# SCH_New-Project_2024-08-15.net
KiCad netlist of a schematic drawn in EasyEDA
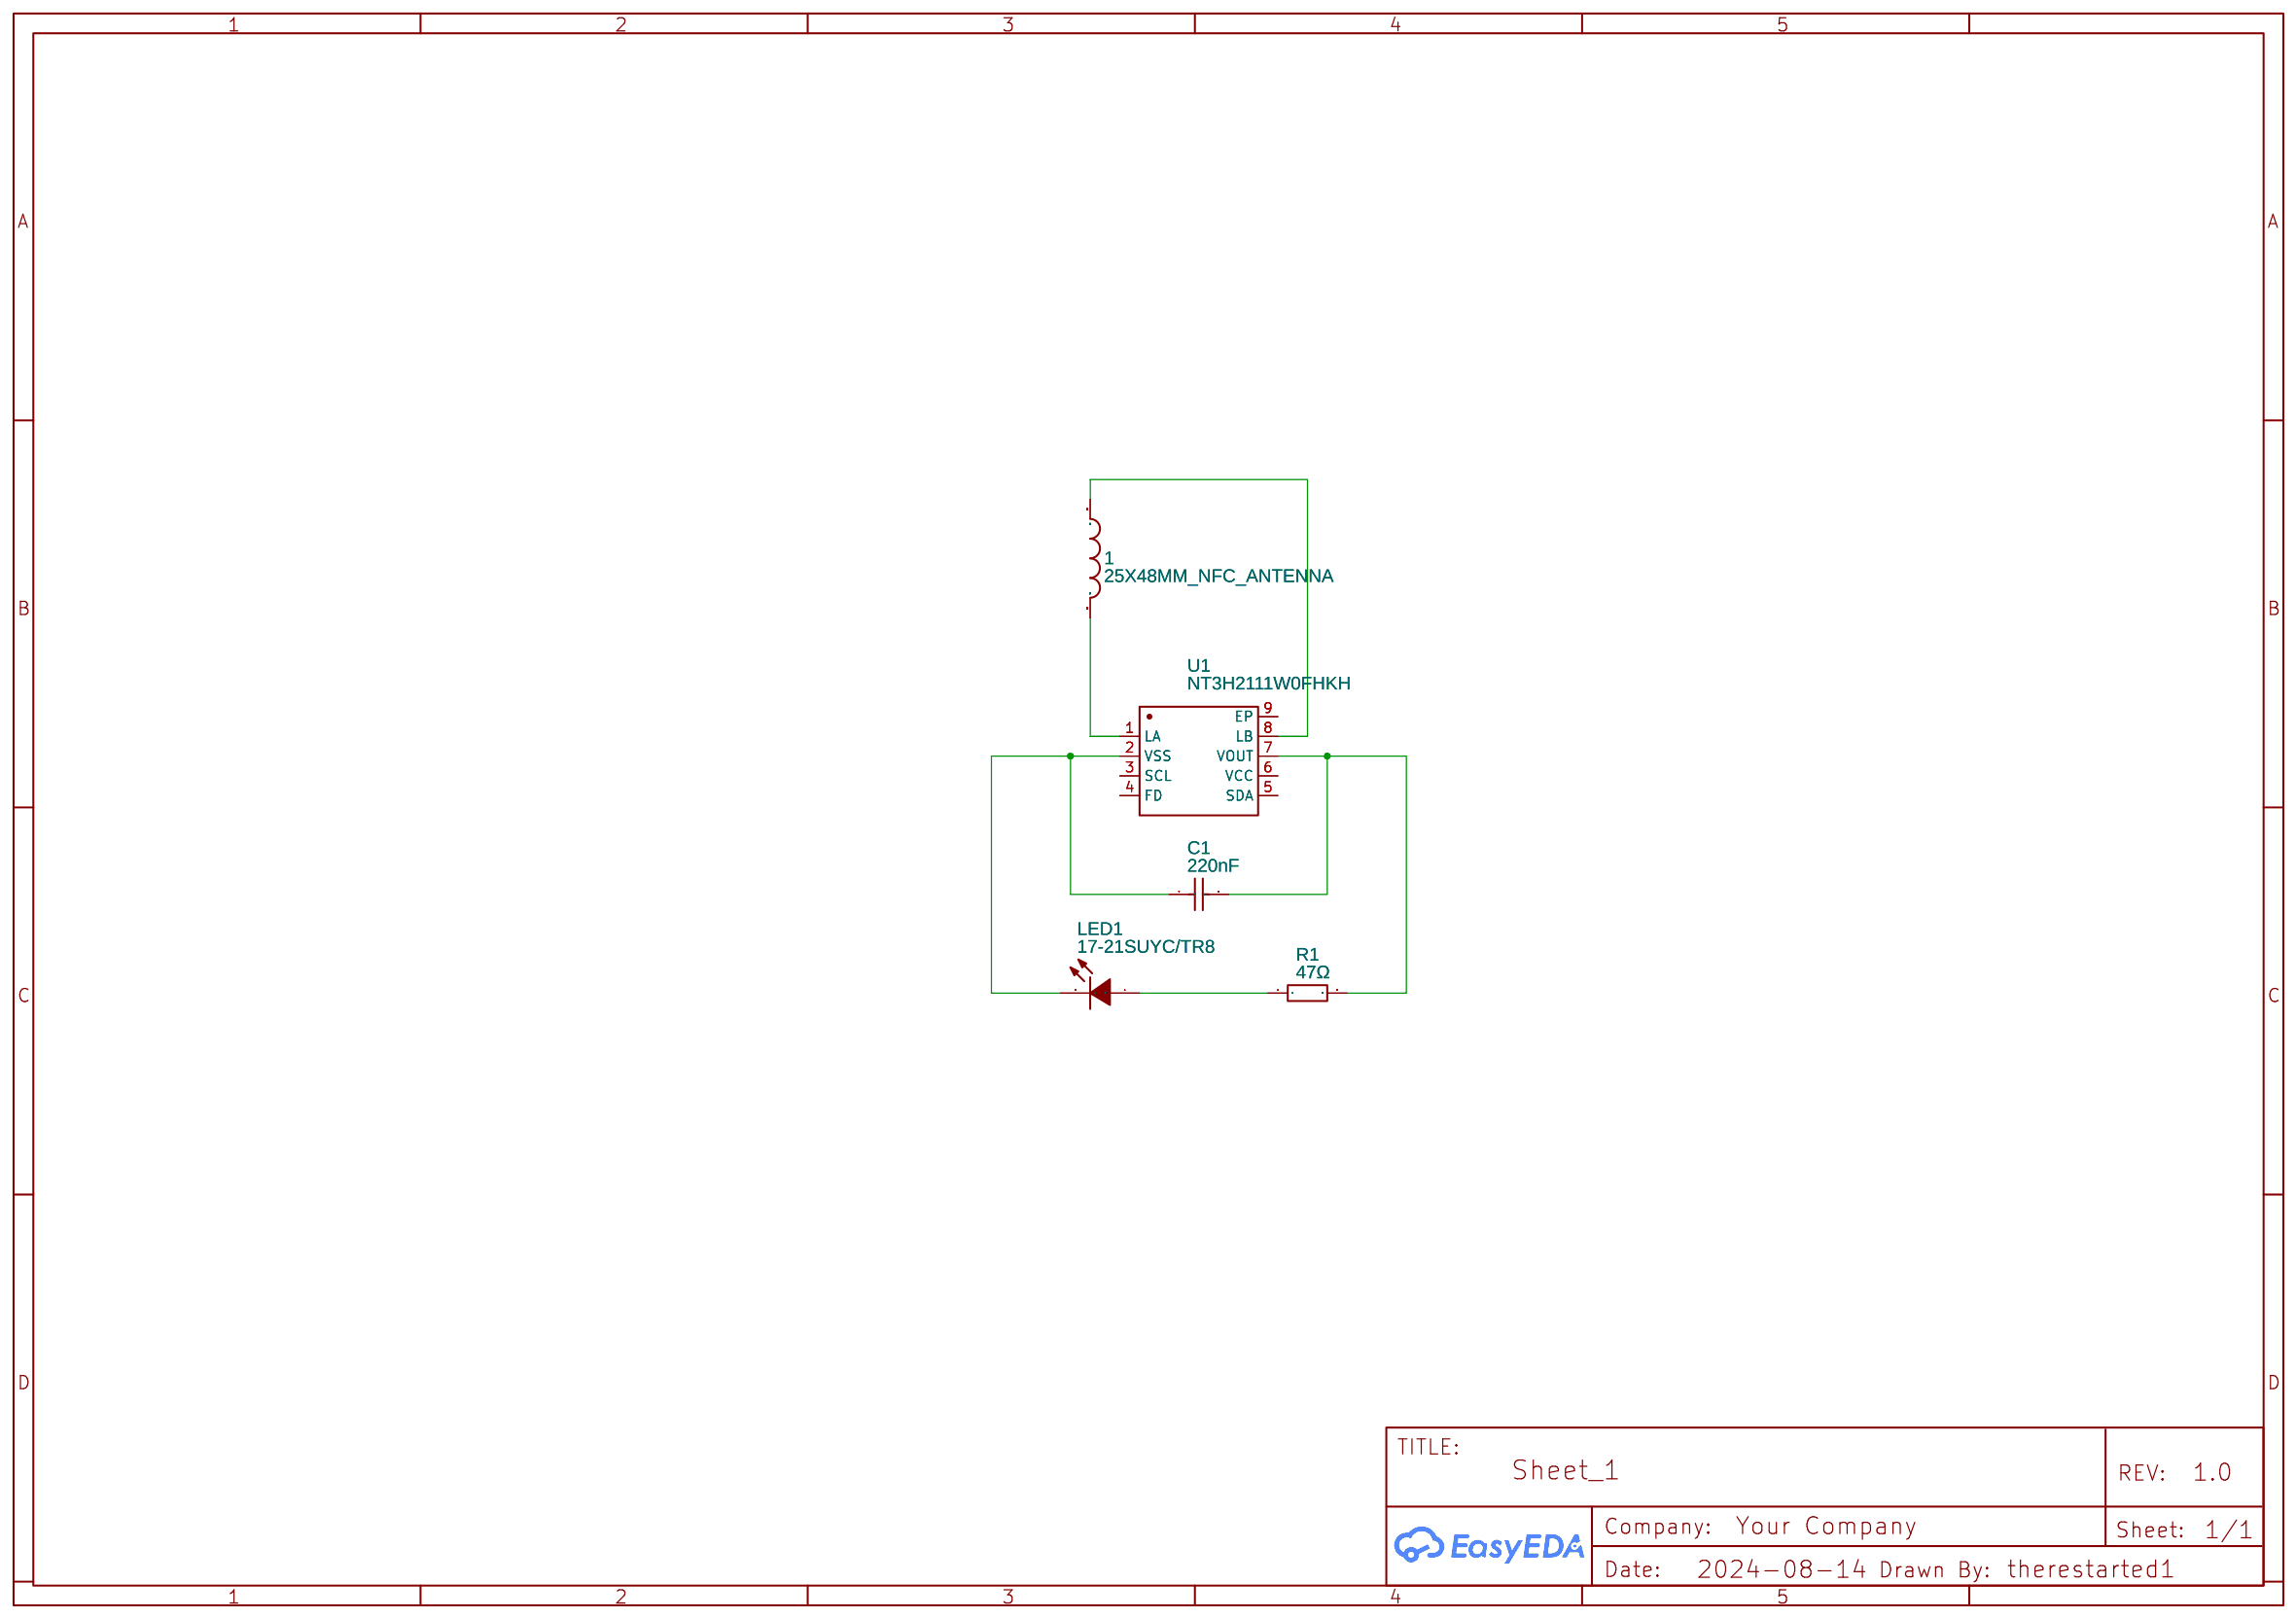
[diagram p0: schematic sheet]

(export (version "E")
  (design (tool "Eeschema 10.0.6"))
  (components
    (comp (ref "1") (value "25X48MM_NFC_ANTENNA") (libsource (lib "") (part "25X48MM_NFC_ANTENNA")))
    (comp (ref "C1")
      (value "220nF")
      (fields
        (field (name "Manufacturer Part") "CL10B224KA8NNNC")
        (field (name "Manufacturer") "SAMSUNG(三星)")
      )
      (libsource (lib "") (part "CL10B224KA8NNNC"))
    )
    (comp (ref "LED1")
      (value "17-21SUYC/TR8")
      (fields (field (name "Manufacturer Part") "KT-0805黄灯") (field (name "Manufacturer") "KENTO"))
      (libsource (lib "") (part "17-21SUYC/TR8"))
    )
    (comp (ref "R1")
      (value "47Ω")
      (fields
        (field (name "Manufacturer Part") "0603WAF470JT5E")
        (field (name "Manufacturer") "UNI-ROYAL(厚声)")
      )
      (libsource (lib "") (part "0603WAF470JT5E"))
    )
    (comp (ref "U1")
      (value "NT3H2111W0FHKH")
      (fields (field (name "Manufacturer") "NXP(恩智浦)"))
      (libsource (lib "") (part "NT3H2111W0FHKH"))
    )
  )
  (nets
    (net (code "1") (name "Net-(LED1-+)") (class "Default")
      (node (ref "LED1") (pin "1") (pinfunction "+_1") (pintype "unspecified"))
      (node (ref "R1") (pin "1") (pinfunction "1_1") (pintype "input"))
    )
    (net (code "2") (name "Net-(LED1--)") (class "Default")
      (node (ref "C1") (pin "1") (pinfunction "1_1") (pintype "input"))
      (node (ref "LED1") (pin "2") (pinfunction "-_2") (pintype "unspecified"))
      (node (ref "U1") (pin "2") (pinfunction "VSS_2") (pintype "unspecified"))
    )
    (net (code "3") (name "Net-(U1-LA)") (class "Default")
      (node (ref "1") (pin "P$2") (pinfunction "P$2_P$2") (pintype "bidirectional"))
      (node (ref "U1") (pin "1") (pinfunction "LA_1") (pintype "unspecified"))
    )
    (net (code "4") (name "Net-(U1-LB)") (class "Default")
      (node (ref "1") (pin "P$1") (pinfunction "P$1_P$1") (pintype "bidirectional"))
      (node (ref "U1") (pin "8") (pinfunction "LB_8") (pintype "unspecified"))
    )
    (net (code "5") (name "Net-(U1-VOUT)") (class "Default")
      (node (ref "C1") (pin "2") (pinfunction "2_2") (pintype "input"))
      (node (ref "R1") (pin "2") (pinfunction "2_2") (pintype "input"))
      (node (ref "U1") (pin "7") (pinfunction "VOUT_7") (pintype "unspecified"))
    )
    (net (code "6") (name "unconnected-(U1-EP-Pad9)") (class "Default")
      (node (ref "U1") (pin "9") (pinfunction "EP_9") (pintype "unspecified"))
    )
    (net (code "7") (name "unconnected-(U1-FD-Pad4)") (class "Default")
      (node (ref "U1") (pin "4") (pinfunction "FD_4") (pintype "unspecified"))
    )
    (net (code "8") (name "unconnected-(U1-SCL-Pad3)") (class "Default")
      (node (ref "U1") (pin "3") (pinfunction "SCL_3") (pintype "unspecified"))
    )
    (net (code "9") (name "unconnected-(U1-SDA-Pad5)") (class "Default")
      (node (ref "U1") (pin "5") (pinfunction "SDA_5") (pintype "unspecified"))
    )
    (net (code "10") (name "unconnected-(U1-VCC-Pad6)") (class "Default")
      (node (ref "U1") (pin "6") (pinfunction "VCC_6") (pintype "unspecified"))
    )
  )
)
